# EXO-IMU3.net
KiCad netlist of a schematic drawn in EasyEDA Pro
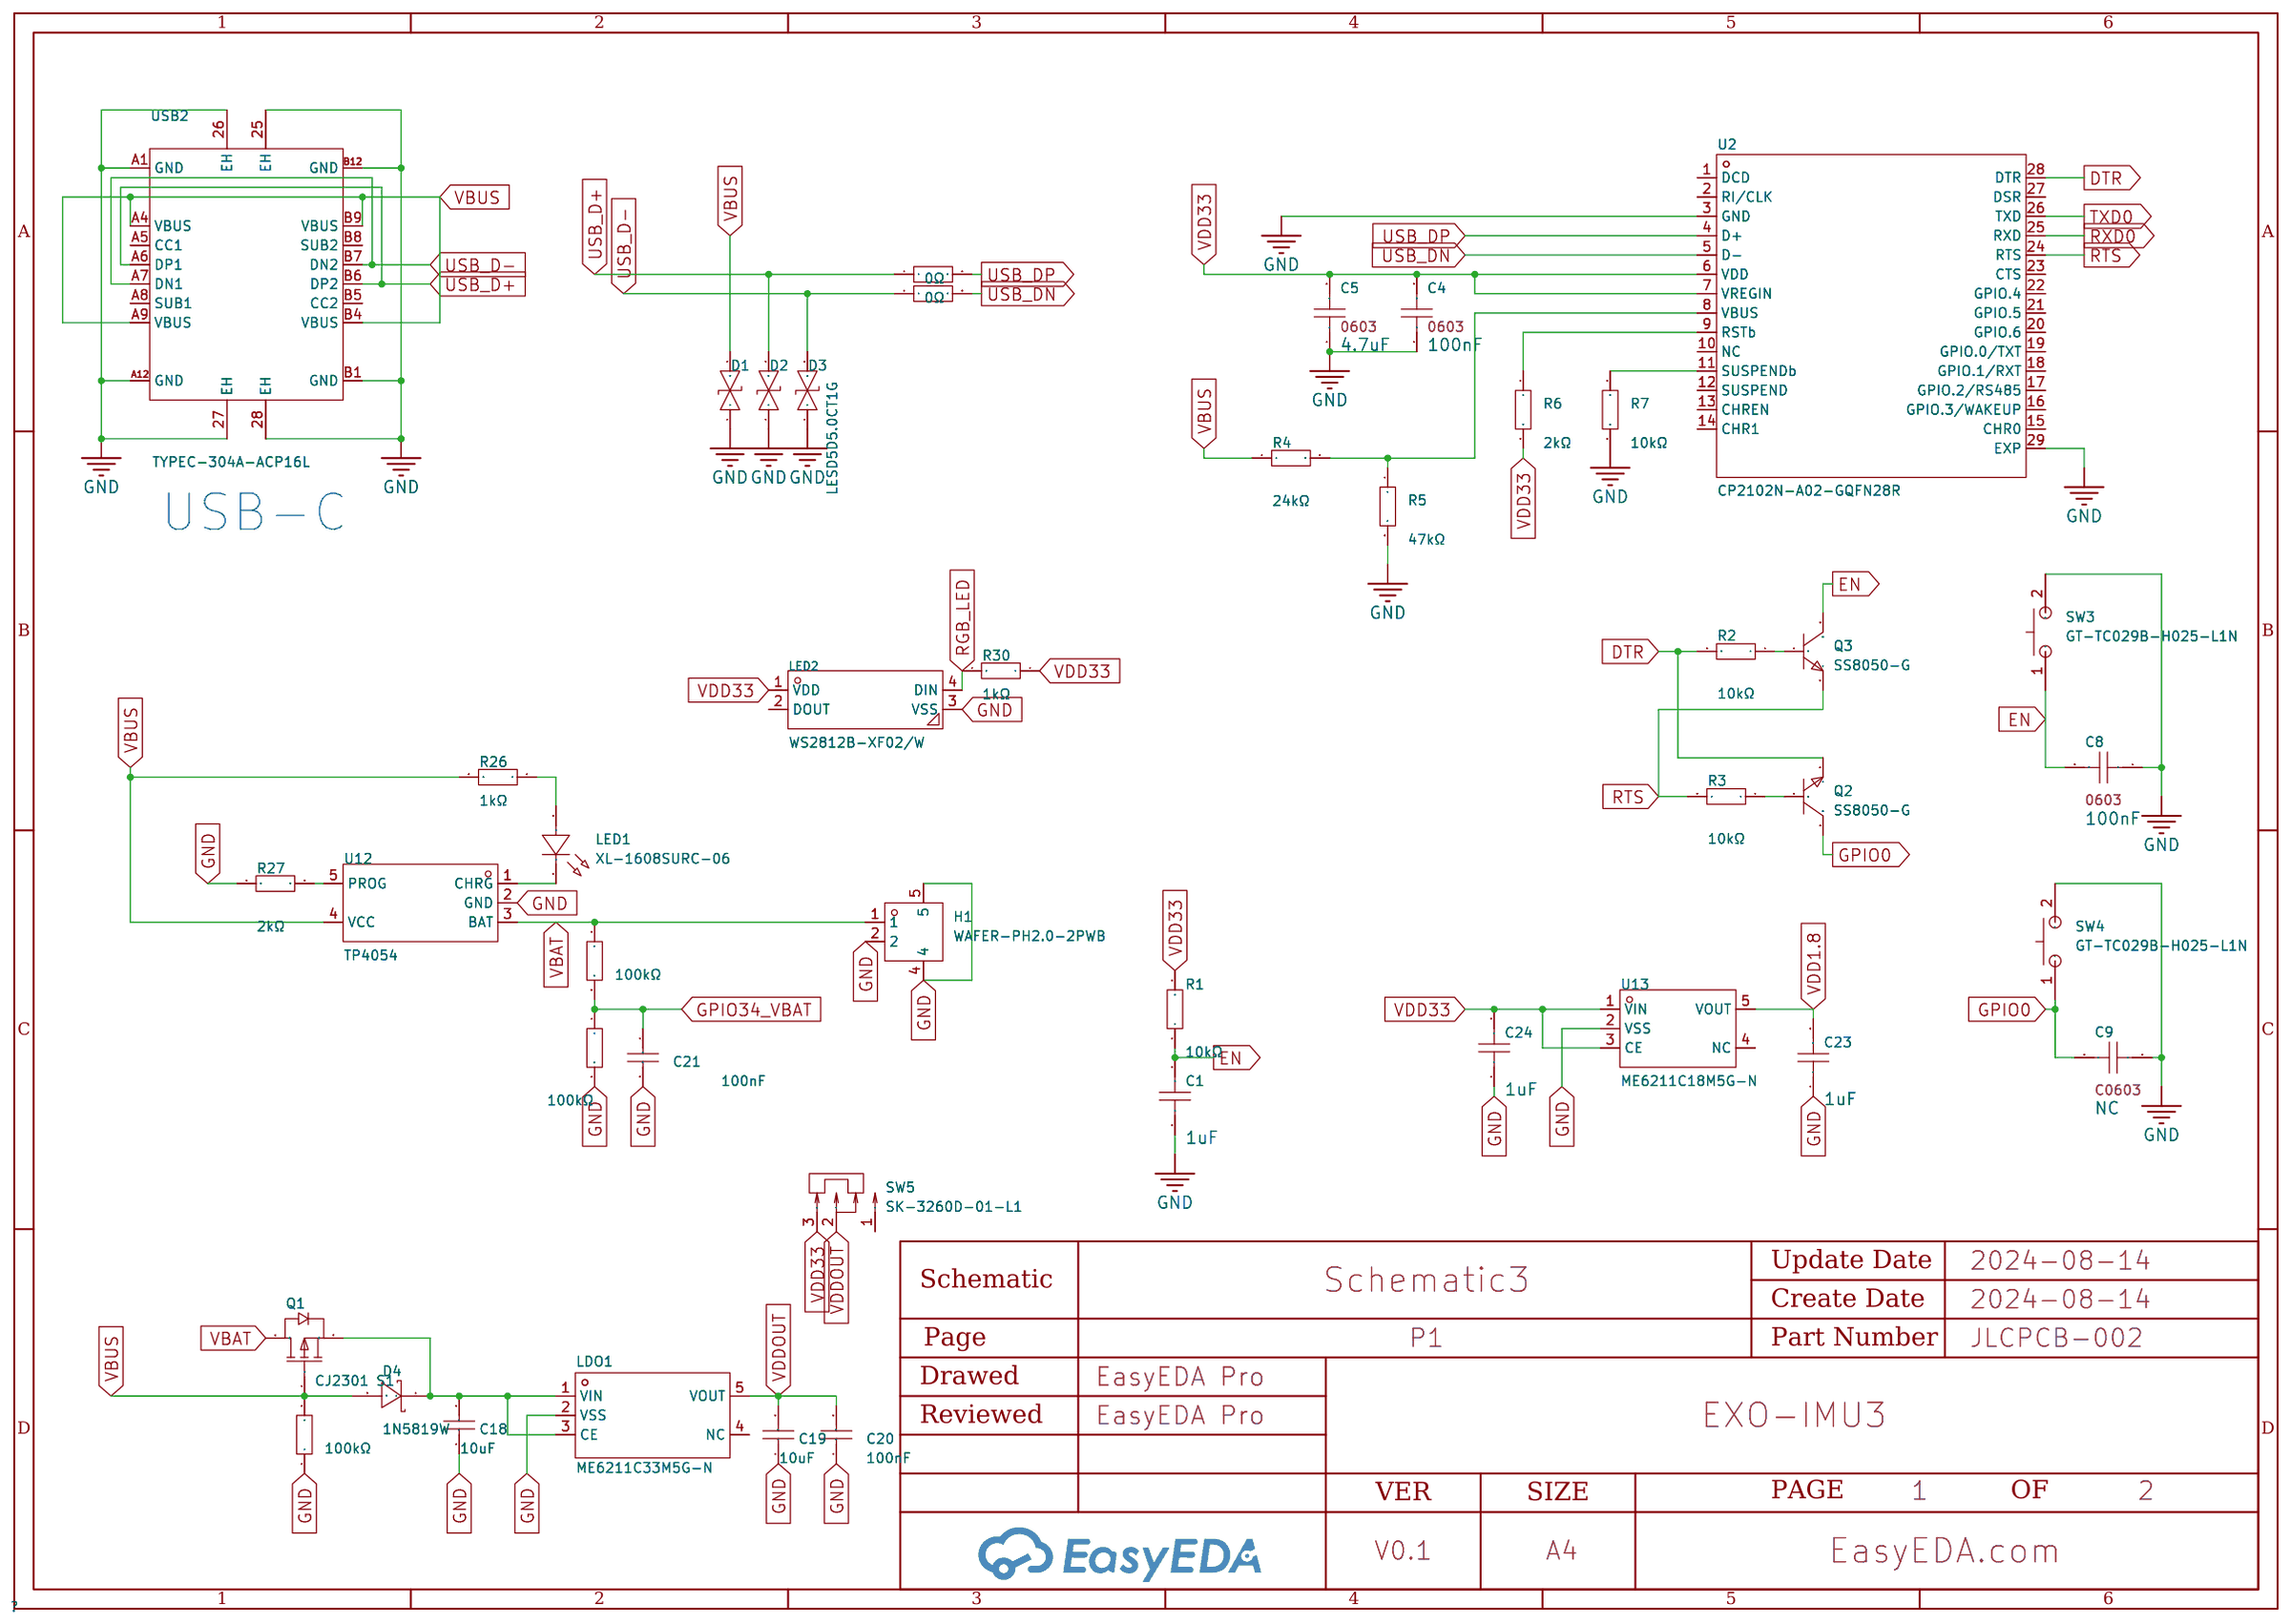
[diagram p0: P1]
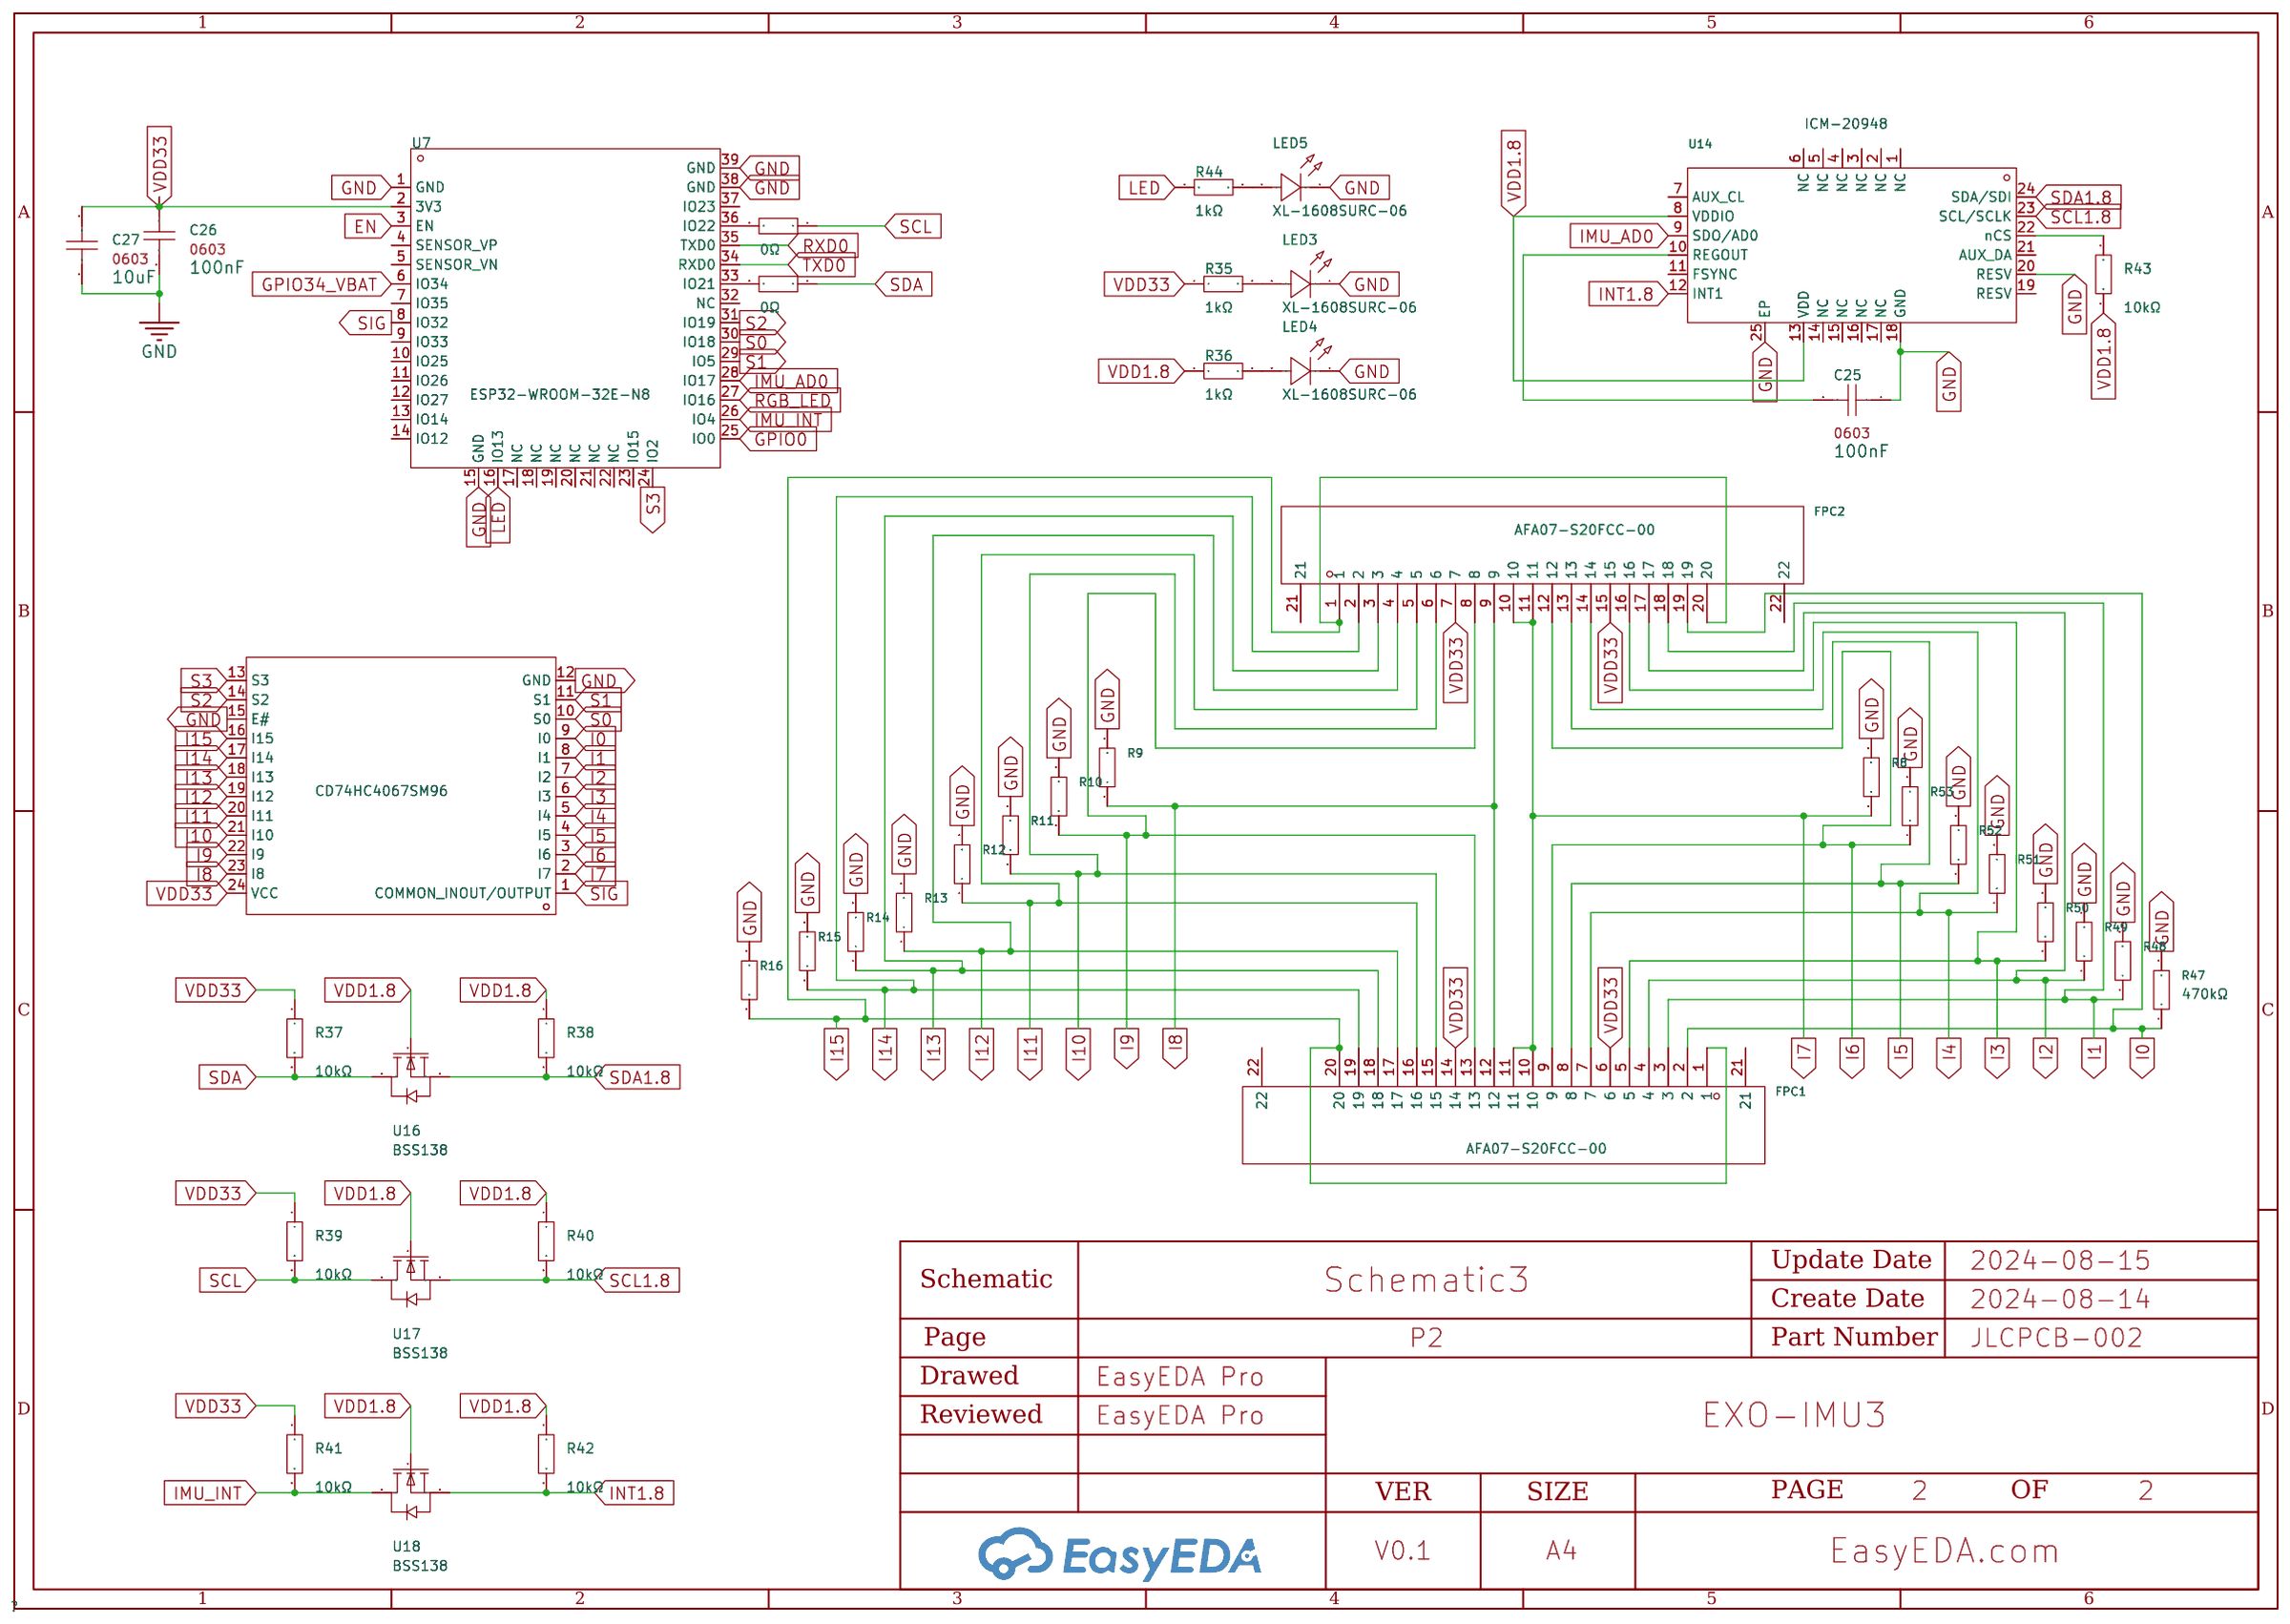
[diagram p1: P2]

(export (version "E")
  (design (tool "Eeschema 10.0.6"))
  (components
    (comp (ref "C1")
      (value "1uF")
      (footprint "easyedapro:C0603")
      (fields
        (field (name "Manufacturer Part") "CL10B105KO8NNNC")
        (field (name "Manufacturer") "SAMSUNG(三星)")
      )
      (libsource (lib "easyedapro") (part "CL10A106KP8NNNC"))
    )
    (comp (ref "C4")
      (value "100nF")
      (footprint "easyedapro:C0603")
      (fields
        (field (name "Manufacturer Part") "CC0603KRX7R6BB104")
        (field (name "Manufacturer") "YAGEO(国巨)")
        (field (name "Supplier Footprint") "0603")
      )
      (libsource (lib "easyedapro") (part "CL10A106KP8NNNC"))
    )
    (comp (ref "C5")
      (value "4.7uF")
      (footprint "easyedapro:C0603")
      (fields
        (field (name "Manufacturer Part") "CL10A475KP8NNNC")
        (field (name "Manufacturer") "SAMSUNG(三星)")
        (field (name "Supplier Footprint") "0603")
      )
      (libsource (lib "easyedapro") (part "CL10A106KP8NNNC"))
    )
    (comp (ref "C8")
      (value "100nF")
      (footprint "easyedapro:C0603")
      (fields
        (field (name "Manufacturer Part") "CC0603KRX7R6BB104")
        (field (name "Manufacturer") "YAGEO(国巨)")
        (field (name "Supplier Footprint") "0603")
      )
      (libsource (lib "easyedapro") (part "CL10A106KP8NNNC"))
    )
    (comp (ref "C9")
      (value "NC")
      (footprint "easyedapro:C0603")
      (fields (field (name "Manufacturer Part") "0603") (field (name "Supplier Footprint") "C0603"))
      (libsource (lib "easyedapro") (part "CL10A106KP8NNNC"))
    )
    (comp (ref "C18")
      (value "10uF")
      (fields
        (field (name "Manufacturer Part") "CL10A106KP8NNNC")
        (field (name "Manufacturer") "SAMSUNG(三星)")
      )
      (libsource (lib "easyedapro") (part "CL10A106MO8NQNC"))
    )
    (comp (ref "C19")
      (value "10uF")
      (fields
        (field (name "Manufacturer Part") "CL10A106KP8NNNC")
        (field (name "Manufacturer") "SAMSUNG(三星)")
      )
      (libsource (lib "easyedapro") (part "CL10A106MO8NQNC"))
    )
    (comp (ref "C20")
      (value "100nF")
      (fields
        (field (name "Manufacturer Part") "CC0603KRX7R6BB104")
        (field (name "Manufacturer") "YAGEO(国巨)")
      )
      (libsource (lib "easyedapro") (part "CL10B104KO8NNNC"))
    )
    (comp (ref "C21")
      (value "100nF")
      (fields
        (field (name "Manufacturer Part") "CC0603KRX7R6BB104")
        (field (name "Manufacturer") "YAGEO(国巨)")
      )
      (libsource (lib "easyedapro") (part "CL10B104KO8NNNC"))
    )
    (comp (ref "C23")
      (value "1uF")
      (footprint "easyedapro:C0603")
      (fields
        (field (name "Manufacturer Part") "CL10B105KO8NNNC")
        (field (name "Manufacturer") "SAMSUNG(三星)")
      )
      (libsource (lib "easyedapro") (part "CL10A106KP8NNNC"))
    )
    (comp (ref "C24")
      (value "1uF")
      (footprint "easyedapro:C0603")
      (fields
        (field (name "Manufacturer Part") "CL10B105KO8NNNC")
        (field (name "Manufacturer") "SAMSUNG(三星)")
      )
      (libsource (lib "easyedapro") (part "CL10A106KP8NNNC"))
    )
    (comp (ref "D1")
      (value "LESD5D5.0CT1G")
      (footprint "easyedapro:SOD-523_L1.2-W0.8-LS1.6-BI")
      (fields (field (name "Manufacturer") "LRC(乐山无线电)"))
      (libsource (lib "easyedapro") (part "LESD5D5.0CT1G"))
    )
    (comp (ref "D2")
      (value "LESD5D5.0CT1G")
      (footprint "easyedapro:SOD-523_L1.2-W0.8-LS1.6-BI")
      (fields (field (name "Manufacturer") "LRC(乐山无线电)"))
      (libsource (lib "easyedapro") (part "LESD5D5.0CT1G"))
    )
    (comp (ref "D3")
      (value "LESD5D5.0CT1G")
      (footprint "easyedapro:SOD-523_L1.2-W0.8-LS1.6-BI")
      (fields (field (name "Manufacturer") "LRC(乐山无线电)"))
      (libsource (lib "easyedapro") (part "LESD5D5.0CT1G"))
    )
    (comp (ref "D4")
      (value "1N5819W")
      (footprint "easyedapro:SOD-123F_L2.8-W1.8-LS3.7-RD")
      (description "Reverse Voltage (Vr):40V Average Rectified Current (Io):1A Forward Voltage (Vf@If):600mV@1A")
      (fields (field (name "Manufacturer") "晶导微电子"))
      (libsource (lib "easyedapro") (part "1N5819W"))
    )
    (comp (ref "H1")
      (value "WAFER-PH2.0-2PWB")
      (footprint "easyedapro:CONN-SMD_2P-P2.00_XUNPU_WAFER-PH2.0-2PWB")
      (fields (field (name "Manufacturer") "XUNPU(讯普)"))
      (libsource (lib "easyedapro") (part "WAFER-PH2.0-2PWB"))
    )
    (comp (ref "LDO1")
      (value "ME6211C33M5G-N")
      (footprint "easyedapro:SOT-23-5_L3.0-W1.7-P0.95-LS2.8-BL")
      (fields (field (name "Manufacturer") "MICRONE(南京微盟)"))
      (libsource (lib "easyedapro") (part "ME6211C33M5G-N"))
    )
    (comp (ref "LED1")
      (value "XL-1608SURC-06")
      (footprint "easyedapro:LED0603-RD_RED")
      (fields (field (name "Manufacturer") "XINGLIGHT(成兴光)"))
      (libsource (lib "easyedapro") (part "XL-1608SURC-06"))
    )
    (comp (ref "LED2")
      (value "WS2812B-XF02/W")
      (footprint "easyedapro:LED-SMD_4P-L5.0-W5.0-TL")
      (fields (field (name "Manufacturer") "worldsemi"))
      (libsource (lib "easyedapro") (part "WS2812B-XF02/W"))
    )
    (comp (ref "Q1")
      (value "CJ2301 S1")
      (footprint "easyedapro:SOT-23-3_L3.0-W1.7-P0.95-LS2.9-BR")
      (fields (field (name "Manufacturer") "CJ(江苏长电/长晶)"))
      (libsource (lib "easyedapro") (part "CJ2301 S1"))
    )
    (comp (ref "Q2")
      (value "SS8050-G")
      (footprint "easyedapro:SOT-23-3_L2.9-W1.3-P1.90-LS2.4-BR")
      (fields (field (name "Manufacturer") "CJ（江苏长电/长晶）"))
      (libsource (lib "easyedapro") (part "SS8050-G_C164885"))
    )
    (comp (ref "Q3")
      (value "SS8050-G")
      (footprint "easyedapro:SOT-23-3_L2.9-W1.3-P1.90-LS2.4-BR")
      (fields (field (name "Manufacturer") "CJ（江苏长电/长晶）"))
      (libsource (lib "easyedapro") (part "SS8050-G_C164885"))
    )
    (comp (ref "R1")
      (value "10kΩ")
      (footprint "easyedapro:R0603")
      (fields (field (name "Manufacturer Part") "RC0603JR-0710KL") (field (name "Manufacturer") "YAGEO(国巨)"))
      (libsource (lib "easyedapro") (part "0603WAF0000T5E"))
    )
    (comp (ref "R2")
      (value "10kΩ")
      (footprint "easyedapro:R0603")
      (fields (field (name "Manufacturer Part") "RC0603JR-0710KL") (field (name "Manufacturer") "YAGEO(国巨)"))
      (libsource (lib "easyedapro") (part "0603WAF0000T5E"))
    )
    (comp (ref "R3")
      (value "10kΩ")
      (footprint "easyedapro:R0603")
      (fields (field (name "Manufacturer Part") "RC0603JR-0710KL") (field (name "Manufacturer") "YAGEO(国巨)"))
      (libsource (lib "easyedapro") (part "0603WAF0000T5E"))
    )
    (comp (ref "R4")
      (value "24kΩ")
      (footprint "easyedapro:R0603")
      (fields
        (field (name "Manufacturer Part") "0603WAF2402T5E")
        (field (name "Manufacturer") "UNI-ROYAL(厚声)")
      )
      (libsource (lib "easyedapro") (part "RC0603JR-0710KL"))
    )
    (comp (ref "R5")
      (value "47kΩ")
      (footprint "easyedapro:R0603")
      (fields (field (name "Manufacturer Part") "RC0603FR-0747KL") (field (name "Manufacturer") "YAGEO(国巨)"))
      (libsource (lib "easyedapro") (part "RC0603JR-0710KL"))
    )
    (comp (ref "R6")
      (value "2kΩ")
      (footprint "easyedapro:R0603")
      (fields
        (field (name "Manufacturer Part") "0603WAF2001T5E")
        (field (name "Manufacturer") "UNI-ROYAL(厚声)")
      )
      (libsource (lib "easyedapro") (part "RC0603JR-0710KL"))
    )
    (comp (ref "R7")
      (value "10kΩ")
      (footprint "easyedapro:R0603")
      (fields (field (name "Manufacturer Part") "RC0603JR-0710KL") (field (name "Manufacturer") "YAGEO(国巨)"))
      (libsource (lib "easyedapro") (part "0603WAF0000T5E"))
    )
    (comp (ref "R21")
      (value "0Ω")
      (footprint "easyedapro:R0603")
      (fields
        (field (name "Manufacturer Part") "0603WAF0000T5E")
        (field (name "Manufacturer") "UNI-ROYAL(厚声)")
      )
      (libsource (lib "easyedapro") (part "RC0603JR-0710KL"))
    )
    (comp (ref "R22")
      (value "0Ω")
      (footprint "easyedapro:R0603")
      (fields
        (field (name "Manufacturer Part") "0603WAF0000T5E")
        (field (name "Manufacturer") "UNI-ROYAL(厚声)")
      )
      (libsource (lib "easyedapro") (part "RC0603JR-0710KL"))
    )
    (comp (ref "R25")
      (value "100kΩ")
      (footprint "easyedapro:R0603")
      (fields
        (field (name "Manufacturer Part") "0603WAF1003T5E")
        (field (name "Manufacturer") "UNI-ROYAL(厚声)")
      )
      (libsource (lib "easyedapro") (part "RC0603JR-0710KL"))
    )
    (comp (ref "R26")
      (value "1kΩ")
      (footprint "easyedapro:R0603")
      (fields
        (field (name "Manufacturer Part") "0603WAF1001T5E")
        (field (name "Manufacturer") "UNI-ROYAL(厚声)")
      )
      (libsource (lib "easyedapro") (part "0603WAF1001T5E"))
    )
    (comp (ref "R27")
      (value "2kΩ")
      (footprint "easyedapro:R0603")
      (fields
        (field (name "Manufacturer Part") "0603WAF2001T5E")
        (field (name "Manufacturer") "UNI-ROYAL(厚声)")
      )
      (libsource (lib "easyedapro") (part "RC0603JR-0710KL"))
    )
    (comp (ref "R28")
      (value "100kΩ")
      (footprint "easyedapro:R0603")
      (fields
        (field (name "Manufacturer Part") "0603WAF1003T5E")
        (field (name "Manufacturer") "UNI-ROYAL(厚声)")
      )
      (libsource (lib "easyedapro") (part "RC0603JR-0710KL"))
    )
    (comp (ref "R29")
      (value "100kΩ")
      (footprint "easyedapro:R0603")
      (fields
        (field (name "Manufacturer Part") "0603WAF1003T5E")
        (field (name "Manufacturer") "UNI-ROYAL(厚声)")
      )
      (libsource (lib "easyedapro") (part "RC0603JR-0710KL"))
    )
    (comp (ref "R30")
      (value "1kΩ")
      (footprint "easyedapro:R0603")
      (fields
        (field (name "Manufacturer Part") "0603WAF1001T5E")
        (field (name "Manufacturer") "UNI-ROYAL(厚声)")
      )
      (libsource (lib "easyedapro") (part "0603WAF1001T5E"))
    )
    (comp (ref "SW3")
      (value "GT-TC029B-H025-L1N")
      (footprint "easyedapro:SW-SMD_L3.9-W3.0-P4.45")
      (fields (field (name "Manufacturer") "G-Switch(品赞)"))
      (libsource (lib "easyedapro") (part "GT-TC029B-H025-L1N"))
    )
    (comp (ref "SW4")
      (value "GT-TC029B-H025-L1N")
      (footprint "easyedapro:SW-SMD_L3.9-W3.0-P4.45")
      (fields (field (name "Manufacturer") "G-Switch(品赞)"))
      (libsource (lib "easyedapro") (part "GT-TC029B-H025-L1N"))
    )
    (comp (ref "SW5")
      (value "SK-3260D-01-L1")
      (footprint "easyedapro:SW-TH_SK-3260D-01-LX")
      (fields (field (name "Manufacturer") "XKB Connectivity(中国星坤)"))
      (libsource (lib "easyedapro") (part "SK-3260D-01-L1"))
    )
    (comp (ref "U2")
      (value "CP2102N-A02-GQFN28R")
      (fields (field (name "Manufacturer") "SILICON LABS(芯科)"))
      (libsource (lib "easyedapro") (part "CP2102N-A01-GQFN28"))
    )
    (comp (ref "U12")
      (value "TP4054")
      (footprint "easyedapro:SOT-23-5_L2.9-W1.6-P0.95-LS2.8-BR")
      (fields (field (name "Manufacturer") "JSMSEMI(杰盛微)"))
      (libsource (lib "easyedapro") (part "TP4054_C5381776"))
    )
    (comp (ref "U13")
      (value "ME6211C18M5G-N")
      (footprint "easyedapro:SOT-23-5_L3.0-W1.7-P0.95-LS2.8-BR")
      (fields (field (name "Manufacturer") "MICRONE(南京微盟)"))
      (libsource (lib "easyedapro") (part "ME6211C18M5G-N"))
    )
    (comp (ref "USB2")
      (value "TYPEC-304A-ACP16L")
      (footprint "easyedapro:USB-C-SMD_XUNPU_TYPEC-304A-ACP16L")
      (fields (field (name "Manufacturer") "XUNPU(讯普)"))
      (libsource (lib "easyedapro") (part "TYPEC-304A-ACP16L"))
    )
    (comp (ref "C25")
      (value "100nF")
      (footprint "easyedapro:C0603")
      (fields
        (field (name "Manufacturer Part") "CC0603KRX7R6BB104")
        (field (name "Manufacturer") "YAGEO(国巨)")
        (field (name "Supplier Footprint") "0603")
      )
      (libsource (lib "easyedapro") (part "CL10A106KP8NNNC"))
    )
    (comp (ref "C26")
      (value "100nF")
      (footprint "easyedapro:C0603")
      (fields
        (field (name "Manufacturer Part") "CC0603KRX7R6BB104")
        (field (name "Manufacturer") "YAGEO(国巨)")
        (field (name "Supplier Footprint") "0603")
      )
      (libsource (lib "easyedapro") (part "0603_C9900021180"))
    )
    (comp (ref "C27")
      (value "10uF")
      (footprint "easyedapro:C0603")
      (fields
        (field (name "Manufacturer Part") "CL10A106KP8NNNC")
        (field (name "Manufacturer") "SAMSUNG(三星)")
        (field (name "Supplier Footprint") "0603")
      )
      (libsource (lib "easyedapro") (part "0603_C9900021180"))
    )
    (comp (ref "FPC1")
      (value "AFA07-S20FCC-00")
      (footprint "easyedapro:FPC-SMD_AFA07-S20FCC-00")
      (fields (field (name "Manufacturer") "JS(钜硕电子)"))
      (libsource (lib "easyedapro") (part "AFA07-S20FCC-00"))
    )
    (comp (ref "FPC2")
      (value "AFA07-S20FCC-00")
      (footprint "easyedapro:FPC-SMD_AFA07-S20FCC-00")
      (fields (field (name "Manufacturer") "JS(钜硕电子)"))
      (libsource (lib "easyedapro") (part "AFA07-S20FCC-00"))
    )
    (comp (ref "LED3")
      (value "XL-1608SURC-06")
      (footprint "easyedapro:LED0603-RD_RED")
      (fields (field (name "Manufacturer") "XINGLIGHT(成兴光)"))
      (libsource (lib "easyedapro") (part "XL-1608SURC-06"))
    )
    (comp (ref "LED4")
      (value "XL-1608SURC-06")
      (footprint "easyedapro:LED0603-RD_RED")
      (fields (field (name "Manufacturer") "XINGLIGHT(成兴光)"))
      (libsource (lib "easyedapro") (part "XL-1608SURC-06"))
    )
    (comp (ref "LED5")
      (value "XL-1608SURC-06")
      (footprint "easyedapro:LED0603-RD_RED")
      (fields (field (name "Manufacturer") "XINGLIGHT(成兴光)"))
      (libsource (lib "easyedapro") (part "XL-1608SURC-06"))
    )
    (comp (ref "R8")
      (value "470kΩ")
      (footprint "easyedapro:R0805")
      (fields
        (field (name "Manufacturer Part") "0805W8F4703T5E")
        (field (name "Manufacturer") "UNI-ROYAL(厚声)")
      )
      (libsource (lib "easyedapro") (part "0805W8F4703T5E"))
    )
    (comp (ref "R9")
      (value "470kΩ")
      (footprint "easyedapro:R0805")
      (fields
        (field (name "Manufacturer Part") "0805W8F4703T5E")
        (field (name "Manufacturer") "UNI-ROYAL(厚声)")
      )
      (libsource (lib "easyedapro") (part "0805W8F4703T5E"))
    )
    (comp (ref "R10")
      (value "470kΩ")
      (footprint "easyedapro:R0805")
      (fields
        (field (name "Manufacturer Part") "0805W8F4703T5E")
        (field (name "Manufacturer") "UNI-ROYAL(厚声)")
      )
      (libsource (lib "easyedapro") (part "0805W8F4703T5E"))
    )
    (comp (ref "R11")
      (value "470kΩ")
      (footprint "easyedapro:R0805")
      (fields
        (field (name "Manufacturer Part") "0805W8F4703T5E")
        (field (name "Manufacturer") "UNI-ROYAL(厚声)")
      )
      (libsource (lib "easyedapro") (part "0805W8F4703T5E"))
    )
    (comp (ref "R12")
      (value "470kΩ")
      (footprint "easyedapro:R0805")
      (fields
        (field (name "Manufacturer Part") "0805W8F4703T5E")
        (field (name "Manufacturer") "UNI-ROYAL(厚声)")
      )
      (libsource (lib "easyedapro") (part "0805W8F4703T5E"))
    )
    (comp (ref "R13")
      (value "470kΩ")
      (footprint "easyedapro:R0805")
      (fields
        (field (name "Manufacturer Part") "0805W8F4703T5E")
        (field (name "Manufacturer") "UNI-ROYAL(厚声)")
      )
      (libsource (lib "easyedapro") (part "0805W8F4703T5E"))
    )
    (comp (ref "R14")
      (value "470kΩ")
      (footprint "easyedapro:R0805")
      (fields
        (field (name "Manufacturer Part") "0805W8F4703T5E")
        (field (name "Manufacturer") "UNI-ROYAL(厚声)")
      )
      (libsource (lib "easyedapro") (part "0805W8F4703T5E"))
    )
    (comp (ref "R15")
      (value "470kΩ")
      (footprint "easyedapro:R0805")
      (fields
        (field (name "Manufacturer Part") "0805W8F4703T5E")
        (field (name "Manufacturer") "UNI-ROYAL(厚声)")
      )
      (libsource (lib "easyedapro") (part "0805W8F4703T5E"))
    )
    (comp (ref "R16")
      (value "470kΩ")
      (footprint "easyedapro:R0805")
      (fields
        (field (name "Manufacturer Part") "0805W8F4703T5E")
        (field (name "Manufacturer") "UNI-ROYAL(厚声)")
      )
      (libsource (lib "easyedapro") (part "0805W8F4703T5E"))
    )
    (comp (ref "R35")
      (value "1kΩ")
      (footprint "easyedapro:R0603")
      (fields
        (field (name "Manufacturer Part") "0603WAF1001T5E")
        (field (name "Manufacturer") "UNI-ROYAL(厚声)")
      )
      (libsource (lib "easyedapro") (part "0603WAF1001T5E"))
    )
    (comp (ref "R36")
      (value "1kΩ")
      (footprint "easyedapro:R0603")
      (fields
        (field (name "Manufacturer Part") "0603WAF1001T5E")
        (field (name "Manufacturer") "UNI-ROYAL(厚声)")
      )
      (libsource (lib "easyedapro") (part "0603WAF1001T5E"))
    )
    (comp (ref "R37")
      (value "10kΩ")
      (footprint "easyedapro:R0603")
      (fields (field (name "Manufacturer Part") "RC0603JR-0710KL") (field (name "Manufacturer") "YAGEO(国巨)"))
      (libsource (lib "easyedapro") (part "0603WAF0000T5E"))
    )
    (comp (ref "R38")
      (value "10kΩ")
      (footprint "easyedapro:R0603")
      (fields (field (name "Manufacturer Part") "RC0603JR-0710KL") (field (name "Manufacturer") "YAGEO(国巨)"))
      (libsource (lib "easyedapro") (part "0603WAF0000T5E"))
    )
    (comp (ref "R39")
      (value "10kΩ")
      (footprint "easyedapro:R0603")
      (fields (field (name "Manufacturer Part") "RC0603JR-0710KL") (field (name "Manufacturer") "YAGEO(国巨)"))
      (libsource (lib "easyedapro") (part "0603WAF0000T5E"))
    )
    (comp (ref "R40")
      (value "10kΩ")
      (footprint "easyedapro:R0603")
      (fields (field (name "Manufacturer Part") "RC0603JR-0710KL") (field (name "Manufacturer") "YAGEO(国巨)"))
      (libsource (lib "easyedapro") (part "0603WAF0000T5E"))
    )
    (comp (ref "R41")
      (value "10kΩ")
      (footprint "easyedapro:R0603")
      (fields (field (name "Manufacturer Part") "RC0603JR-0710KL") (field (name "Manufacturer") "YAGEO(国巨)"))
      (libsource (lib "easyedapro") (part "0603WAF0000T5E"))
    )
    (comp (ref "R42")
      (value "10kΩ")
      (footprint "easyedapro:R0603")
      (fields (field (name "Manufacturer Part") "RC0603JR-0710KL") (field (name "Manufacturer") "YAGEO(国巨)"))
      (libsource (lib "easyedapro") (part "0603WAF0000T5E"))
    )
    (comp (ref "R43")
      (value "10kΩ")
      (footprint "easyedapro:R0603")
      (fields (field (name "Manufacturer Part") "RC0603JR-0710KL") (field (name "Manufacturer") "YAGEO(国巨)"))
      (libsource (lib "easyedapro") (part "0603WAF0000T5E"))
    )
    (comp (ref "R44")
      (value "1kΩ")
      (footprint "easyedapro:R0603")
      (fields
        (field (name "Manufacturer Part") "0603WAF1001T5E")
        (field (name "Manufacturer") "UNI-ROYAL(厚声)")
      )
      (libsource (lib "easyedapro") (part "0603WAF1001T5E"))
    )
    (comp (ref "R45")
      (value "0Ω")
      (footprint "easyedapro:R0603")
      (fields
        (field (name "Manufacturer Part") "0603WAF0000T5E")
        (field (name "Manufacturer") "UNI-ROYAL(厚声)")
      )
      (libsource (lib "easyedapro") (part "RC0603JR-0710KL"))
    )
    (comp (ref "R46")
      (value "0Ω")
      (footprint "easyedapro:R0603")
      (fields
        (field (name "Manufacturer Part") "0603WAF0000T5E")
        (field (name "Manufacturer") "UNI-ROYAL(厚声)")
      )
      (libsource (lib "easyedapro") (part "RC0603JR-0710KL"))
    )
    (comp (ref "R47")
      (value "470kΩ")
      (footprint "easyedapro:R0805")
      (fields
        (field (name "Manufacturer Part") "0805W8F4703T5E")
        (field (name "Manufacturer") "UNI-ROYAL(厚声)")
      )
      (libsource (lib "easyedapro") (part "0805W8F4703T5E"))
    )
    (comp (ref "R48")
      (value "470kΩ")
      (footprint "easyedapro:R0805")
      (fields
        (field (name "Manufacturer Part") "0805W8F4703T5E")
        (field (name "Manufacturer") "UNI-ROYAL(厚声)")
      )
      (libsource (lib "easyedapro") (part "0805W8F4703T5E"))
    )
    (comp (ref "R49")
      (value "470kΩ")
      (footprint "easyedapro:R0805")
      (fields
        (field (name "Manufacturer Part") "0805W8F4703T5E")
        (field (name "Manufacturer") "UNI-ROYAL(厚声)")
      )
      (libsource (lib "easyedapro") (part "0805W8F4703T5E"))
    )
    (comp (ref "R50")
      (value "470kΩ")
      (footprint "easyedapro:R0805")
      (fields
        (field (name "Manufacturer Part") "0805W8F4703T5E")
        (field (name "Manufacturer") "UNI-ROYAL(厚声)")
      )
      (libsource (lib "easyedapro") (part "0805W8F4703T5E"))
    )
    (comp (ref "R51")
      (value "470kΩ")
      (footprint "easyedapro:R0805")
      (fields
        (field (name "Manufacturer Part") "0805W8F4703T5E")
        (field (name "Manufacturer") "UNI-ROYAL(厚声)")
      )
      (libsource (lib "easyedapro") (part "0805W8F4703T5E"))
    )
    (comp (ref "R52")
      (value "470kΩ")
      (footprint "easyedapro:R0805")
      (fields
        (field (name "Manufacturer Part") "0805W8F4703T5E")
        (field (name "Manufacturer") "UNI-ROYAL(厚声)")
      )
      (libsource (lib "easyedapro") (part "0805W8F4703T5E"))
    )
    (comp (ref "R53")
      (value "470kΩ")
      (footprint "easyedapro:R0805")
      (fields
        (field (name "Manufacturer Part") "0805W8F4703T5E")
        (field (name "Manufacturer") "UNI-ROYAL(厚声)")
      )
      (libsource (lib "easyedapro") (part "0805W8F4703T5E"))
    )
    (comp (ref "U7")
      (value "ESP32-WROOM-32E-N8")
      (footprint "easyedapro:WIFI-SMD_ESP32-WROOM-32E")
      (fields (field (name "Manufacturer") "ESPRESSIF(乐鑫)"))
      (libsource (lib "easyedapro") (part "ESP32-WROOM-32E-N8"))
    )
    (comp (ref "U14")
      (value "ICM-20948")
      (footprint "easyedapro:QFN-24_L3.0-W3.0-P0.40-BL-EP")
      (description "Sensor Type:加速度计陀螺仪 Operating Temperature:-40°C~+85°C Operating Temperature:-40°C~+85°C")
      (fields (field (name "Manufacturer") "TDK InvenSense(应美盛)"))
      (libsource (lib "easyedapro") (part "ICM-20948"))
    )
    (comp (ref "U16")
      (value "BSS138")
      (footprint "easyedapro:SOT-23-3_L2.9-W1.3-P1.90-LS2.4-BR")
      (fields (field (name "Manufacturer") "宏迦橙"))
      (libsource (lib "easyedapro") (part "BSS138_C7420339"))
    )
    (comp (ref "U17")
      (value "BSS138")
      (footprint "easyedapro:SOT-23-3_L2.9-W1.3-P1.90-LS2.4-BR")
      (fields (field (name "Manufacturer") "宏迦橙"))
      (libsource (lib "easyedapro") (part "BSS138_C7420339"))
    )
    (comp (ref "U18")
      (value "BSS138")
      (footprint "easyedapro:SOT-23-3_L2.9-W1.3-P1.90-LS2.4-BR")
      (fields (field (name "Manufacturer") "宏迦橙"))
      (libsource (lib "easyedapro") (part "BSS138_C7420339"))
    )
    (comp (ref "U19")
      (value "CD74HC4067SM96")
      (footprint "easyedapro:SSOP-24_L8.1-W5.3-P0.65-LS7.8-BL")
      (description "Switch Circuit:-")
      (fields (field (name "Manufacturer") "TI(德州仪器)"))
      (libsource (lib "easyedapro") (part "CD74HC4067SM96"))
    )
  )
  (nets
    (net (code "1") (name "DTR") (class "Default")
      (node (ref "Q2") (pin "2") (pinfunction "E_2") (pintype "input"))
      (node (ref "R2") (pin "2") (pinfunction "2_2") (pintype "input"))
      (node (ref "U2") (pin "28") (pinfunction "DTR_28") (pintype "input"))
    )
    (net (code "2") (name "EN") (class "Default")
      (node (ref "C1") (pin "2") (pinfunction "2_2") (pintype "input"))
      (node (ref "C8") (pin "2") (pinfunction "2_2") (pintype "input"))
      (node (ref "Q3") (pin "3") (pinfunction "C_3") (pintype "input"))
      (node (ref "R1") (pin "1") (pinfunction "1_1") (pintype "input"))
      (node (ref "SW3") (pin "1") (pinfunction "1_1") (pintype "input"))
      (node (ref "U7") (pin "3") (pinfunction "EN_3") (pintype "input"))
    )
    (net (code "3") (name "GND") (class "Default")
      (node (ref "C1") (pin "1") (pinfunction "1_1") (pintype "input"))
      (node (ref "C18") (pin "1") (pinfunction "1_1") (pintype "input"))
      (node (ref "C19") (pin "1") (pinfunction "1_1") (pintype "input"))
      (node (ref "C20") (pin "1") (pinfunction "1_1") (pintype "input"))
      (node (ref "C21") (pin "2") (pinfunction "2_2") (pintype "input"))
      (node (ref "C23") (pin "1") (pinfunction "1_1") (pintype "input"))
      (node (ref "C24") (pin "1") (pinfunction "1_1") (pintype "input"))
      (node (ref "C25") (pin "1") (pinfunction "1_1") (pintype "input"))
      (node (ref "C26") (pin "1") (pinfunction "1_1") (pintype "input"))
      (node (ref "C27") (pin "1") (pinfunction "1_1") (pintype "input"))
      (node (ref "C4") (pin "1") (pinfunction "1_1") (pintype "input"))
      (node (ref "C5") (pin "1") (pinfunction "1_1") (pintype "input"))
      (node (ref "C8") (pin "1") (pinfunction "1_1") (pintype "input"))
      (node (ref "C9") (pin "1") (pinfunction "1_1") (pintype "input"))
      (node (ref "D1") (pin "1") (pinfunction "1_1") (pintype "input"))
      (node (ref "D2") (pin "1") (pinfunction "1_1") (pintype "input"))
      (node (ref "D3") (pin "1") (pinfunction "1_1") (pintype "input"))
      (node (ref "H1") (pin "2") (pinfunction "2_2") (pintype "input"))
      (node (ref "H1") (pin "4") (pinfunction "4_4") (pintype "input"))
      (node (ref "H1") (pin "5") (pinfunction "5_5") (pintype "input"))
      (node (ref "LDO1") (pin "2") (pinfunction "VSS_2") (pintype "input"))
      (node (ref "LED2") (pin "3") (pinfunction "VSS_3") (pintype "input"))
      (node (ref "LED3") (pin "1") (pinfunction "K_1") (pintype "input"))
      (node (ref "LED4") (pin "1") (pinfunction "K_1") (pintype "input"))
      (node (ref "LED5") (pin "1") (pinfunction "K_1") (pintype "input"))
      (node (ref "R10") (pin "2") (pinfunction "2_2") (pintype "input"))
      (node (ref "R11") (pin "2") (pinfunction "2_2") (pintype "input"))
      (node (ref "R12") (pin "2") (pinfunction "2_2") (pintype "input"))
      (node (ref "R13") (pin "2") (pinfunction "2_2") (pintype "input"))
      (node (ref "R14") (pin "2") (pinfunction "2_2") (pintype "input"))
      (node (ref "R15") (pin "2") (pinfunction "2_2") (pintype "input"))
      (node (ref "R16") (pin "2") (pinfunction "2_2") (pintype "input"))
      (node (ref "R25") (pin "1") (pinfunction "1_1") (pintype "input"))
      (node (ref "R27") (pin "1") (pinfunction "1_1") (pintype "input"))
      (node (ref "R28") (pin "2") (pinfunction "2_2") (pintype "input"))
      (node (ref "R47") (pin "2") (pinfunction "2_2") (pintype "input"))
      (node (ref "R48") (pin "2") (pinfunction "2_2") (pintype "input"))
      (node (ref "R49") (pin "2") (pinfunction "2_2") (pintype "input"))
      (node (ref "R5") (pin "2") (pinfunction "2_2") (pintype "input"))
      (node (ref "R50") (pin "2") (pinfunction "2_2") (pintype "input"))
      (node (ref "R51") (pin "2") (pinfunction "2_2") (pintype "input"))
      (node (ref "R52") (pin "2") (pinfunction "2_2") (pintype "input"))
      (node (ref "R53") (pin "2") (pinfunction "2_2") (pintype "input"))
      (node (ref "R7") (pin "2") (pinfunction "2_2") (pintype "input"))
      (node (ref "R8") (pin "2") (pinfunction "2_2") (pintype "input"))
      (node (ref "R9") (pin "2") (pinfunction "2_2") (pintype "input"))
      (node (ref "SW3") (pin "2") (pinfunction "2_2") (pintype "input"))
      (node (ref "SW4") (pin "2") (pinfunction "2_2") (pintype "input"))
      (node (ref "U12") (pin "2") (pinfunction "GND_2") (pintype "input"))
      (node (ref "U13") (pin "2") (pinfunction "VSS_2") (pintype "input"))
      (node (ref "U14") (pin "18") (pinfunction "GND_18") (pintype "input"))
      (node (ref "U14") (pin "20") (pinfunction "RESV_20") (pintype "input"))
      (node (ref "U14") (pin "25") (pinfunction "EP_25") (pintype "input"))
      (node (ref "U19") (pin "12") (pinfunction "GND_12") (pintype "unspecified"))
      (node (ref "U19") (pin "15") (pinfunction "E#_15") (pintype "unspecified"))
      (node (ref "U2") (pin "29") (pinfunction "EXP_29") (pintype "input"))
      (node (ref "U2") (pin "3") (pinfunction "GND_3") (pintype "input"))
      (node (ref "U7") (pin "1") (pinfunction "GND_1") (pintype "input"))
      (node (ref "U7") (pin "15") (pinfunction "GND_15") (pintype "input"))
      (node (ref "U7") (pin "38") (pinfunction "GND_38") (pintype "input"))
      (node (ref "U7") (pin "39") (pinfunction "GND_39") (pintype "input"))
      (node (ref "USB2") (pin "25") (pinfunction "EH_25") (pintype "input"))
      (node (ref "USB2") (pin "26") (pinfunction "EH_26") (pintype "input"))
      (node (ref "USB2") (pin "27") (pinfunction "EH_27") (pintype "input"))
      (node (ref "USB2") (pin "28") (pinfunction "EH_28") (pintype "input"))
      (node (ref "USB2") (pin "A1") (pinfunction "GND_A1") (pintype "input"))
      (node (ref "USB2") (pin "A12") (pinfunction "GND_A12") (pintype "input"))
      (node (ref "USB2") (pin "B1") (pinfunction "GND_B1") (pintype "input"))
      (node (ref "USB2") (pin "B12") (pinfunction "GND_B12") (pintype "input"))
    )
    (net (code "4") (name "GPIO0") (class "Default")
      (node (ref "C9") (pin "2") (pinfunction "2_2") (pintype "input"))
      (node (ref "Q2") (pin "3") (pinfunction "C_3") (pintype "input"))
      (node (ref "SW4") (pin "1") (pinfunction "1_1") (pintype "input"))
      (node (ref "U7") (pin "25") (pinfunction "IO0_25") (pintype "input"))
    )
    (net (code "5") (name "GPIO34_VBAT") (class "Default")
      (node (ref "C21") (pin "1") (pinfunction "1_1") (pintype "input"))
      (node (ref "R28") (pin "1") (pinfunction "1_1") (pintype "input"))
      (node (ref "R29") (pin "2") (pinfunction "2_2") (pintype "input"))
      (node (ref "U7") (pin "6") (pinfunction "IO34_6") (pintype "input"))
    )
    (net (code "6") (name "I0") (class "Default")
      (node (ref "FPC1") (pin "2") (pinfunction "2_2") (pintype "input"))
      (node (ref "FPC2") (pin "19") (pinfunction "19_19") (pintype "input"))
      (node (ref "R47") (pin "1") (pinfunction "1_1") (pintype "input"))
      (node (ref "U19") (pin "9") (pinfunction "I0_9") (pintype "unspecified"))
    )
    (net (code "7") (name "I1") (class "Default")
      (node (ref "FPC1") (pin "3") (pinfunction "3_3") (pintype "input"))
      (node (ref "FPC2") (pin "18") (pinfunction "18_18") (pintype "input"))
      (node (ref "R48") (pin "1") (pinfunction "1_1") (pintype "input"))
      (node (ref "U19") (pin "8") (pinfunction "I1_8") (pintype "unspecified"))
    )
    (net (code "8") (name "I2") (class "Default")
      (node (ref "FPC1") (pin "4") (pinfunction "4_4") (pintype "input"))
      (node (ref "FPC2") (pin "17") (pinfunction "17_17") (pintype "input"))
      (node (ref "R49") (pin "1") (pinfunction "1_1") (pintype "input"))
      (node (ref "U19") (pin "7") (pinfunction "I2_7") (pintype "unspecified"))
    )
    (net (code "9") (name "I3") (class "Default")
      (node (ref "FPC1") (pin "5") (pinfunction "5_5") (pintype "input"))
      (node (ref "FPC2") (pin "16") (pinfunction "16_16") (pintype "input"))
      (node (ref "R50") (pin "1") (pinfunction "1_1") (pintype "input"))
      (node (ref "U19") (pin "6") (pinfunction "I3_6") (pintype "unspecified"))
    )
    (net (code "10") (name "I4") (class "Default")
      (node (ref "FPC1") (pin "7") (pinfunction "7_7") (pintype "input"))
      (node (ref "FPC2") (pin "14") (pinfunction "14_14") (pintype "input"))
      (node (ref "R51") (pin "1") (pinfunction "1_1") (pintype "input"))
      (node (ref "U19") (pin "5") (pinfunction "I4_5") (pintype "unspecified"))
    )
    (net (code "11") (name "I5") (class "Default")
      (node (ref "FPC1") (pin "8") (pinfunction "8_8") (pintype "input"))
      (node (ref "FPC2") (pin "13") (pinfunction "13_13") (pintype "input"))
      (node (ref "R52") (pin "1") (pinfunction "1_1") (pintype "input"))
      (node (ref "U19") (pin "4") (pinfunction "I5_4") (pintype "unspecified"))
    )
    (net (code "12") (name "I6") (class "Default")
      (node (ref "FPC1") (pin "9") (pinfunction "9_9") (pintype "input"))
      (node (ref "FPC2") (pin "12") (pinfunction "12_12") (pintype "input"))
      (node (ref "R53") (pin "1") (pinfunction "1_1") (pintype "input"))
      (node (ref "U19") (pin "3") (pinfunction "I6_3") (pintype "unspecified"))
    )
    (net (code "13") (name "I7") (class "Default")
      (node (ref "FPC1") (pin "10") (pinfunction "10_10") (pintype "input"))
      (node (ref "FPC1") (pin "11") (pinfunction "11_11") (pintype "input"))
      (node (ref "FPC2") (pin "10") (pinfunction "10_10") (pintype "input"))
      (node (ref "FPC2") (pin "11") (pinfunction "11_11") (pintype "input"))
      (node (ref "R8") (pin "1") (pinfunction "1_1") (pintype "input"))
      (node (ref "U19") (pin "2") (pinfunction "I7_2") (pintype "unspecified"))
    )
    (net (code "14") (name "I8") (class "Default")
      (node (ref "FPC1") (pin "12") (pinfunction "12_12") (pintype "input"))
      (node (ref "FPC2") (pin "9") (pinfunction "9_9") (pintype "input"))
      (node (ref "R9") (pin "1") (pinfunction "1_1") (pintype "input"))
      (node (ref "U19") (pin "23") (pinfunction "I8_23") (pintype "unspecified"))
    )
    (net (code "15") (name "I9") (class "Default")
      (node (ref "FPC1") (pin "13") (pinfunction "13_13") (pintype "input"))
      (node (ref "FPC2") (pin "8") (pinfunction "8_8") (pintype "input"))
      (node (ref "R10") (pin "1") (pinfunction "1_1") (pintype "input"))
      (node (ref "U19") (pin "22") (pinfunction "I9_22") (pintype "unspecified"))
    )
    (net (code "16") (name "I10") (class "Default")
      (node (ref "FPC1") (pin "15") (pinfunction "15_15") (pintype "input"))
      (node (ref "FPC2") (pin "6") (pinfunction "6_6") (pintype "input"))
      (node (ref "R11") (pin "1") (pinfunction "1_1") (pintype "input"))
      (node (ref "U19") (pin "21") (pinfunction "I10_21") (pintype "unspecified"))
    )
    (net (code "17") (name "I11") (class "Default")
      (node (ref "FPC1") (pin "16") (pinfunction "16_16") (pintype "input"))
      (node (ref "FPC2") (pin "5") (pinfunction "5_5") (pintype "input"))
      (node (ref "R12") (pin "1") (pinfunction "1_1") (pintype "input"))
      (node (ref "U19") (pin "20") (pinfunction "I11_20") (pintype "unspecified"))
    )
    (net (code "18") (name "I12") (class "Default")
      (node (ref "FPC1") (pin "17") (pinfunction "17_17") (pintype "input"))
      (node (ref "FPC2") (pin "4") (pinfunction "4_4") (pintype "input"))
      (node (ref "R13") (pin "1") (pinfunction "1_1") (pintype "input"))
      (node (ref "U19") (pin "19") (pinfunction "I12_19") (pintype "unspecified"))
    )
    (net (code "19") (name "I13") (class "Default")
      (node (ref "FPC1") (pin "18") (pinfunction "18_18") (pintype "input"))
      (node (ref "FPC2") (pin "3") (pinfunction "3_3") (pintype "input"))
      (node (ref "R14") (pin "1") (pinfunction "1_1") (pintype "input"))
      (node (ref "U19") (pin "18") (pinfunction "I13_18") (pintype "unspecified"))
    )
    (net (code "20") (name "I14") (class "Default")
      (node (ref "FPC1") (pin "19") (pinfunction "19_19") (pintype "input"))
      (node (ref "FPC2") (pin "2") (pinfunction "2_2") (pintype "input"))
      (node (ref "R15") (pin "1") (pinfunction "1_1") (pintype "input"))
      (node (ref "U19") (pin "17") (pinfunction "I14_17") (pintype "unspecified"))
    )
    (net (code "21") (name "I15") (class "Default")
      (node (ref "FPC1") (pin "1") (pinfunction "1_1") (pintype "input"))
      (node (ref "FPC1") (pin "20") (pinfunction "20_20") (pintype "input"))
      (node (ref "FPC2") (pin "1") (pinfunction "1_1") (pintype "input"))
      (node (ref "FPC2") (pin "20") (pinfunction "20_20") (pintype "input"))
      (node (ref "R16") (pin "1") (pinfunction "1_1") (pintype "input"))
      (node (ref "U19") (pin "16") (pinfunction "I15_16") (pintype "unspecified"))
    )
    (net (code "22") (name "IMU_AD0") (class "Default")
      (node (ref "U14") (pin "9") (pinfunction "SDO/AD0_9") (pintype "input"))
      (node (ref "U7") (pin "28") (pinfunction "IO17_28") (pintype "input"))
    )
    (net (code "23") (name "IMU_INT") (class "Default")
      (node (ref "R41") (pin "2") (pinfunction "2_2") (pintype "input"))
      (node (ref "U18") (pin "3") (pinfunction "D_3") (pintype "input"))
      (node (ref "U7") (pin "26") (pinfunction "IO4_26") (pintype "input"))
    )
    (net (code "24") (name "INT1.8") (class "Default")
      (node (ref "R42") (pin "2") (pinfunction "2_2") (pintype "input"))
      (node (ref "U14") (pin "12") (pinfunction "INT1_12") (pintype "input"))
      (node (ref "U18") (pin "2") (pinfunction "S_2") (pintype "input"))
    )
    (net (code "25") (name "LED") (class "Default")
      (node (ref "R44") (pin "1") (pinfunction "1_1") (pintype "input"))
      (node (ref "U7") (pin "16") (pinfunction "IO13_16") (pintype "input"))
    )
    (net (code "26") (name "Net-(LDO1-CE)") (class "Default")
      (node (ref "C18") (pin "2") (pinfunction "2_2") (pintype "input"))
      (node (ref "D4") (pin "1") (pinfunction "1_1") (pintype "input"))
      (node (ref "LDO1") (pin "1") (pinfunction "VIN_1") (pintype "input"))
      (node (ref "LDO1") (pin "3") (pinfunction "CE_3") (pintype "input"))
      (node (ref "Q1") (pin "2") (pinfunction "S_2") (pintype "input"))
    )
    (net (code "27") (name "Net-(LED1-A)") (class "Default")
      (node (ref "LED1") (pin "2") (pinfunction "A_2") (pintype "input"))
      (node (ref "R26") (pin "1") (pinfunction "1_1") (pintype "input"))
    )
    (net (code "28") (name "Net-(LED1-K)") (class "Default")
      (node (ref "LED1") (pin "1") (pinfunction "K_1") (pintype "input"))
      (node (ref "U12") (pin "1") (pinfunction "CHRG_1") (pintype "input"))
    )
    (net (code "29") (name "Net-(LED3-A)") (class "Default")
      (node (ref "LED3") (pin "2") (pinfunction "A_2") (pintype "input"))
      (node (ref "R35") (pin "2") (pinfunction "2_2") (pintype "input"))
    )
    (net (code "30") (name "Net-(LED4-A)") (class "Default")
      (node (ref "LED4") (pin "2") (pinfunction "A_2") (pintype "input"))
      (node (ref "R36") (pin "2") (pinfunction "2_2") (pintype "input"))
    )
    (net (code "31") (name "Net-(LED5-A)") (class "Default")
      (node (ref "LED5") (pin "2") (pinfunction "A_2") (pintype "input"))
      (node (ref "R44") (pin "2") (pinfunction "2_2") (pintype "input"))
    )
    (net (code "32") (name "Net-(Q2-B)") (class "Default")
      (node (ref "Q2") (pin "1") (pinfunction "B_1") (pintype "input"))
      (node (ref "R3") (pin "1") (pinfunction "1_1") (pintype "input"))
    )
    (net (code "33") (name "Net-(Q3-B)") (class "Default")
      (node (ref "Q3") (pin "1") (pinfunction "B_1") (pintype "input"))
      (node (ref "R2") (pin "1") (pinfunction "1_1") (pintype "input"))
    )
    (net (code "34") (name "Net-(U2-RSTb)") (class "Default")
      (node (ref "R6") (pin "1") (pinfunction "1_1") (pintype "input"))
      (node (ref "U2") (pin "9") (pinfunction "RSTb_9") (pintype "input"))
    )
    (net (code "35") (name "Net-(U2-SUSPENDb)") (class "Default")
      (node (ref "R7") (pin "1") (pinfunction "1_1") (pintype "input"))
      (node (ref "U2") (pin "11") (pinfunction "SUSPENDb_11") (pintype "input"))
    )
    (net (code "36") (name "Net-(U2-VBUS)") (class "Default")
      (node (ref "R4") (pin "2") (pinfunction "2_2") (pintype "input"))
      (node (ref "R5") (pin "1") (pinfunction "1_1") (pintype "input"))
      (node (ref "U2") (pin "8") (pinfunction "VBUS_8") (pintype "input"))
    )
    (net (code "37") (name "Net-(U7-IO21)") (class "Default")
      (node (ref "R46") (pin "2") (pinfunction "2_2") (pintype "input"))
      (node (ref "U7") (pin "33") (pinfunction "IO21_33") (pintype "input"))
    )
    (net (code "38") (name "Net-(U7-IO22)") (class "Default")
      (node (ref "R45") (pin "2") (pinfunction "2_2") (pintype "input"))
      (node (ref "U7") (pin "36") (pinfunction "IO22_36") (pintype "input"))
    )
    (net (code "39") (name "Net-(U12-PROG)") (class "Default")
      (node (ref "R27") (pin "2") (pinfunction "2_2") (pintype "input"))
      (node (ref "U12") (pin "5") (pinfunction "PROG_5") (pintype "input"))
    )
    (net (code "40") (name "Net-(U14-REGOUT)") (class "Default")
      (node (ref "C25") (pin "2") (pinfunction "2_2") (pintype "input"))
      (node (ref "U14") (pin "10") (pinfunction "REGOUT_10") (pintype "input"))
    )
    (net (code "41") (name "Net-(U14-nCS)") (class "Default")
      (node (ref "R43") (pin "1") (pinfunction "1_1") (pintype "input"))
      (node (ref "U14") (pin "22") (pinfunction "nCS_22") (pintype "input"))
    )
    (net (code "42") (name "RGB_LED") (class "Default")
      (node (ref "LED2") (pin "4") (pinfunction "DIN_4") (pintype "input"))
      (node (ref "R30") (pin "2") (pinfunction "2_2") (pintype "input"))
      (node (ref "U7") (pin "27") (pinfunction "IO16_27") (pintype "input"))
    )
    (net (code "43") (name "RTS") (class "Default")
      (node (ref "Q3") (pin "2") (pinfunction "E_2") (pintype "input"))
      (node (ref "R3") (pin "2") (pinfunction "2_2") (pintype "input"))
      (node (ref "U2") (pin "24") (pinfunction "RTS_24") (pintype "input"))
    )
    (net (code "44") (name "RXD0") (class "Default")
      (node (ref "U2") (pin "25") (pinfunction "RXD_25") (pintype "input"))
      (node (ref "U7") (pin "35") (pinfunction "TXD0_35") (pintype "input"))
    )
    (net (code "45") (name "S0") (class "Default")
      (node (ref "U19") (pin "10") (pinfunction "S0_10") (pintype "unspecified"))
      (node (ref "U7") (pin "30") (pinfunction "IO18_30") (pintype "input"))
    )
    (net (code "46") (name "S1") (class "Default")
      (node (ref "U19") (pin "11") (pinfunction "S1_11") (pintype "unspecified"))
      (node (ref "U7") (pin "29") (pinfunction "IO5_29") (pintype "input"))
    )
    (net (code "47") (name "S2") (class "Default")
      (node (ref "U19") (pin "14") (pinfunction "S2_14") (pintype "unspecified"))
      (node (ref "U7") (pin "31") (pinfunction "IO19_31") (pintype "input"))
    )
    (net (code "48") (name "S3") (class "Default")
      (node (ref "U19") (pin "13") (pinfunction "S3_13") (pintype "unspecified"))
      (node (ref "U7") (pin "24") (pinfunction "IO2_24") (pintype "input"))
    )
    (net (code "49") (name "SCL") (class "Default")
      (node (ref "R39") (pin "2") (pinfunction "2_2") (pintype "input"))
      (node (ref "R45") (pin "1") (pinfunction "1_1") (pintype "input"))
      (node (ref "U17") (pin "3") (pinfunction "D_3") (pintype "input"))
    )
    (net (code "50") (name "SCL1.8") (class "Default")
      (node (ref "R40") (pin "2") (pinfunction "2_2") (pintype "input"))
      (node (ref "U14") (pin "23") (pinfunction "SCL/SCLK_23") (pintype "input"))
      (node (ref "U17") (pin "2") (pinfunction "S_2") (pintype "input"))
    )
    (net (code "51") (name "SDA") (class "Default")
      (node (ref "R37") (pin "2") (pinfunction "2_2") (pintype "input"))
      (node (ref "R46") (pin "1") (pinfunction "1_1") (pintype "input"))
      (node (ref "U16") (pin "3") (pinfunction "D_3") (pintype "input"))
    )
    (net (code "52") (name "SDA1.8") (class "Default")
      (node (ref "R38") (pin "2") (pinfunction "2_2") (pintype "input"))
      (node (ref "U14") (pin "24") (pinfunction "SDA/SDI_24") (pintype "input"))
      (node (ref "U16") (pin "2") (pinfunction "S_2") (pintype "input"))
    )
    (net (code "53") (name "SIG") (class "Default")
      (node (ref "U19") (pin "1") (pinfunction "COMMON_INOUT/OUTPUT_1") (pintype "unspecified"))
      (node (ref "U7") (pin "8") (pinfunction "IO32_8") (pintype "input"))
    )
    (net (code "54") (name "TXD0") (class "Default")
      (node (ref "U2") (pin "26") (pinfunction "TXD_26") (pintype "input"))
      (node (ref "U7") (pin "34") (pinfunction "RXD0_34") (pintype "input"))
    )
    (net (code "55") (name "USB_D+") (class "Default")
      (node (ref "D2") (pin "2") (pinfunction "2_2") (pintype "input"))
      (node (ref "R22") (pin "1") (pinfunction "1_1") (pintype "input"))
      (node (ref "USB2") (pin "A6") (pinfunction "DP1_A6") (pintype "input"))
      (node (ref "USB2") (pin "B6") (pinfunction "DP2_B6") (pintype "input"))
    )
    (net (code "56") (name "USB_D-") (class "Default")
      (node (ref "D3") (pin "2") (pinfunction "2_2") (pintype "input"))
      (node (ref "R21") (pin "1") (pinfunction "1_1") (pintype "input"))
      (node (ref "USB2") (pin "A7") (pinfunction "DN1_A7") (pintype "input"))
      (node (ref "USB2") (pin "B7") (pinfunction "DN2_B7") (pintype "input"))
    )
    (net (code "57") (name "USB_DN") (class "Default")
      (node (ref "R21") (pin "2") (pinfunction "2_2") (pintype "input"))
      (node (ref "U2") (pin "5") (pinfunction "D-_5") (pintype "input"))
    )
    (net (code "58") (name "USB_DP") (class "Default")
      (node (ref "R22") (pin "2") (pinfunction "2_2") (pintype "input"))
      (node (ref "U2") (pin "4") (pinfunction "D+_4") (pintype "input"))
    )
    (net (code "59") (name "VBAT") (class "Default")
      (node (ref "H1") (pin "1") (pinfunction "1_1") (pintype "input"))
      (node (ref "Q1") (pin "3") (pinfunction "D_3") (pintype "input"))
      (node (ref "R29") (pin "1") (pinfunction "1_1") (pintype "input"))
      (node (ref "U12") (pin "3") (pinfunction "BAT_3") (pintype "input"))
    )
    (net (code "60") (name "VBUS") (class "Default")
      (node (ref "D1") (pin "2") (pinfunction "2_2") (pintype "input"))
      (node (ref "D4") (pin "2") (pinfunction "2_2") (pintype "input"))
      (node (ref "Q1") (pin "1") (pinfunction "G_1") (pintype "input"))
      (node (ref "R25") (pin "2") (pinfunction "2_2") (pintype "input"))
      (node (ref "R26") (pin "2") (pinfunction "2_2") (pintype "input"))
      (node (ref "R4") (pin "1") (pinfunction "1_1") (pintype "input"))
      (node (ref "U12") (pin "4") (pinfunction "VCC_4") (pintype "input"))
      (node (ref "USB2") (pin "A4") (pinfunction "VBUS_A4") (pintype "input"))
      (node (ref "USB2") (pin "A9") (pinfunction "VBUS_A9") (pintype "input"))
      (node (ref "USB2") (pin "B4") (pinfunction "VBUS_B4") (pintype "input"))
      (node (ref "USB2") (pin "B9") (pinfunction "VBUS_B9") (pintype "input"))
    )
    (net (code "61") (name "VDD1.8") (class "Default")
      (node (ref "C23") (pin "2") (pinfunction "2_2") (pintype "input"))
      (node (ref "R36") (pin "1") (pinfunction "1_1") (pintype "input"))
      (node (ref "R38") (pin "1") (pinfunction "1_1") (pintype "input"))
      (node (ref "R40") (pin "1") (pinfunction "1_1") (pintype "input"))
      (node (ref "R42") (pin "1") (pinfunction "1_1") (pintype "input"))
      (node (ref "R43") (pin "2") (pinfunction "2_2") (pintype "input"))
      (node (ref "U13") (pin "5") (pinfunction "VOUT_5") (pintype "input"))
      (node (ref "U14") (pin "13") (pinfunction "VDD_13") (pintype "input"))
      (node (ref "U14") (pin "8") (pinfunction "VDDIO_8") (pintype "input"))
      (node (ref "U16") (pin "1") (pinfunction "G_1") (pintype "input"))
      (node (ref "U17") (pin "1") (pinfunction "G_1") (pintype "input"))
      (node (ref "U18") (pin "1") (pinfunction "G_1") (pintype "input"))
    )
    (net (code "62") (name "VDD33") (class "Default")
      (node (ref "C24") (pin "2") (pinfunction "2_2") (pintype "input"))
      (node (ref "C26") (pin "2") (pinfunction "2_2") (pintype "input"))
      (node (ref "C27") (pin "2") (pinfunction "2_2") (pintype "input"))
      (node (ref "C4") (pin "2") (pinfunction "2_2") (pintype "input"))
      (node (ref "C5") (pin "2") (pinfunction "2_2") (pintype "input"))
      (node (ref "FPC1") (pin "14") (pinfunction "14_14") (pintype "input"))
      (node (ref "FPC1") (pin "6") (pinfunction "6_6") (pintype "input"))
      (node (ref "FPC2") (pin "15") (pinfunction "15_15") (pintype "input"))
      (node (ref "FPC2") (pin "7") (pinfunction "7_7") (pintype "input"))
      (node (ref "LED2") (pin "1") (pinfunction "VDD_1") (pintype "input"))
      (node (ref "R1") (pin "2") (pinfunction "2_2") (pintype "input"))
      (node (ref "R30") (pin "1") (pinfunction "1_1") (pintype "input"))
      (node (ref "R35") (pin "1") (pinfunction "1_1") (pintype "input"))
      (node (ref "R37") (pin "1") (pinfunction "1_1") (pintype "input"))
      (node (ref "R39") (pin "1") (pinfunction "1_1") (pintype "input"))
      (node (ref "R41") (pin "1") (pinfunction "1_1") (pintype "input"))
      (node (ref "R6") (pin "2") (pinfunction "2_2") (pintype "input"))
      (node (ref "SW5") (pin "3") (pinfunction "3_3") (pintype "input"))
      (node (ref "U13") (pin "1") (pinfunction "VIN_1") (pintype "input"))
      (node (ref "U13") (pin "3") (pinfunction "CE_3") (pintype "input"))
      (node (ref "U19") (pin "24") (pinfunction "VCC_24") (pintype "unspecified"))
      (node (ref "U2") (pin "6") (pinfunction "VDD_6") (pintype "input"))
      (node (ref "U2") (pin "7") (pinfunction "VREGIN_7") (pintype "input"))
      (node (ref "U7") (pin "2") (pinfunction "3V3_2") (pintype "input"))
    )
    (net (code "63") (name "VDDOUT") (class "Default")
      (node (ref "C19") (pin "2") (pinfunction "2_2") (pintype "input"))
      (node (ref "C20") (pin "2") (pinfunction "2_2") (pintype "input"))
      (node (ref "LDO1") (pin "5") (pinfunction "VOUT_5") (pintype "input"))
      (node (ref "SW5") (pin "2") (pinfunction "2_2") (pintype "input"))
    )
    (net (code "64") (name "unconnected-(FPC1-Pad21)") (class "Default")
      (node (ref "FPC1") (pin "21") (pinfunction "21_21") (pintype "input"))
    )
    (net (code "65") (name "unconnected-(FPC1-Pad22)") (class "Default")
      (node (ref "FPC1") (pin "22") (pinfunction "22_22") (pintype "input"))
    )
    (net (code "66") (name "unconnected-(FPC2-Pad21)") (class "Default")
      (node (ref "FPC2") (pin "21") (pinfunction "21_21") (pintype "input"))
    )
    (net (code "67") (name "unconnected-(FPC2-Pad22)") (class "Default")
      (node (ref "FPC2") (pin "22") (pinfunction "22_22") (pintype "input"))
    )
    (net (code "68") (name "unconnected-(LDO1-NC-Pad4)") (class "Default")
      (node (ref "LDO1") (pin "4") (pinfunction "NC_4") (pintype "input"))
    )
    (net (code "69") (name "unconnected-(LED2-DOUT-Pad2)") (class "Default")
      (node (ref "LED2") (pin "2") (pinfunction "DOUT_2") (pintype "input"))
    )
    (net (code "70") (name "unconnected-(SW5-Pad1)") (class "Default")
      (node (ref "SW5") (pin "1") (pinfunction "1_1") (pintype "input"))
    )
    (net (code "71") (name "unconnected-(U2-CHR0-Pad15)") (class "Default")
      (node (ref "U2") (pin "15") (pinfunction "CHR0_15") (pintype "input"))
    )
    (net (code "72") (name "unconnected-(U2-CHR1-Pad14)") (class "Default")
      (node (ref "U2") (pin "14") (pinfunction "CHR1_14") (pintype "input"))
    )
    (net (code "73") (name "unconnected-(U2-CHREN-Pad13)") (class "Default")
      (node (ref "U2") (pin "13") (pinfunction "CHREN_13") (pintype "input"))
    )
    (net (code "74") (name "unconnected-(U2-CTS-Pad23)") (class "Default")
      (node (ref "U2") (pin "23") (pinfunction "CTS_23") (pintype "input"))
    )
    (net (code "75") (name "unconnected-(U2-DCD-Pad1)") (class "Default")
      (node (ref "U2") (pin "1") (pinfunction "DCD_1") (pintype "input"))
    )
    (net (code "76") (name "unconnected-(U2-DSR-Pad27)") (class "Default")
      (node (ref "U2") (pin "27") (pinfunction "DSR_27") (pintype "input"))
    )
    (net (code "77") (name "unconnected-(U2-GPIO.0{slash}TXT-Pad19)") (class "Default")
      (node (ref "U2") (pin "19") (pinfunction "GPIO.0/TXT_19") (pintype "input"))
    )
    (net (code "78") (name "unconnected-(U2-GPIO.1{slash}RXT-Pad18)") (class "Default")
      (node (ref "U2") (pin "18") (pinfunction "GPIO.1/RXT_18") (pintype "input"))
    )
    (net (code "79") (name "unconnected-(U2-GPIO.2{slash}RS485-Pad17)") (class "Default")
      (node (ref "U2") (pin "17") (pinfunction "GPIO.2/RS485_17") (pintype "input"))
    )
    (net (code "80") (name "unconnected-(U2-GPIO.3{slash}WAKEUP-Pad16)") (class "Default")
      (node (ref "U2") (pin "16") (pinfunction "GPIO.3/WAKEUP_16") (pintype "input"))
    )
    (net (code "81") (name "unconnected-(U2-GPIO.4-Pad22)") (class "Default")
      (node (ref "U2") (pin "22") (pinfunction "GPIO.4_22") (pintype "input"))
    )
    (net (code "82") (name "unconnected-(U2-GPIO.5-Pad21)") (class "Default")
      (node (ref "U2") (pin "21") (pinfunction "GPIO.5_21") (pintype "input"))
    )
    (net (code "83") (name "unconnected-(U2-GPIO.6-Pad20)") (class "Default")
      (node (ref "U2") (pin "20") (pinfunction "GPIO.6_20") (pintype "input"))
    )
    (net (code "84") (name "unconnected-(U2-NC-Pad10)") (class "Default")
      (node (ref "U2") (pin "10") (pinfunction "NC_10") (pintype "input"))
    )
    (net (code "85") (name "unconnected-(U2-RI{slash}CLK-Pad2)") (class "Default")
      (node (ref "U2") (pin "2") (pinfunction "RI/CLK_2") (pintype "input"))
    )
    (net (code "86") (name "unconnected-(U2-SUSPEND-Pad12)") (class "Default")
      (node (ref "U2") (pin "12") (pinfunction "SUSPEND_12") (pintype "input"))
    )
    (net (code "87") (name "unconnected-(U7-IO12-Pad14)") (class "Default")
      (node (ref "U7") (pin "14") (pinfunction "IO12_14") (pintype "input"))
    )
    (net (code "88") (name "unconnected-(U7-IO14-Pad13)") (class "Default")
      (node (ref "U7") (pin "13") (pinfunction "IO14_13") (pintype "input"))
    )
    (net (code "89") (name "unconnected-(U7-IO15-Pad23)") (class "Default")
      (node (ref "U7") (pin "23") (pinfunction "IO15_23") (pintype "input"))
    )
    (net (code "90") (name "unconnected-(U7-IO23-Pad37)") (class "Default")
      (node (ref "U7") (pin "37") (pinfunction "IO23_37") (pintype "input"))
    )
    (net (code "91") (name "unconnected-(U7-IO25-Pad10)") (class "Default")
      (node (ref "U7") (pin "10") (pinfunction "IO25_10") (pintype "input"))
    )
    (net (code "92") (name "unconnected-(U7-IO26-Pad11)") (class "Default")
      (node (ref "U7") (pin "11") (pinfunction "IO26_11") (pintype "input"))
    )
    (net (code "93") (name "unconnected-(U7-IO27-Pad12)") (class "Default")
      (node (ref "U7") (pin "12") (pinfunction "IO27_12") (pintype "input"))
    )
    (net (code "94") (name "unconnected-(U7-IO33-Pad9)") (class "Default")
      (node (ref "U7") (pin "9") (pinfunction "IO33_9") (pintype "input"))
    )
    (net (code "95") (name "unconnected-(U7-IO35-Pad7)") (class "Default")
      (node (ref "U7") (pin "7") (pinfunction "IO35_7") (pintype "input"))
    )
    (net (code "96") (name "unconnected-(U7-NC-Pad17)") (class "Default")
      (node (ref "U7") (pin "17") (pinfunction "NC_17") (pintype "input"))
    )
    (net (code "97") (name "unconnected-(U7-NC-Pad18)") (class "Default")
      (node (ref "U7") (pin "18") (pinfunction "NC_18") (pintype "input"))
    )
    (net (code "98") (name "unconnected-(U7-NC-Pad19)") (class "Default")
      (node (ref "U7") (pin "19") (pinfunction "NC_19") (pintype "input"))
    )
    (net (code "99") (name "unconnected-(U7-NC-Pad20)") (class "Default")
      (node (ref "U7") (pin "20") (pinfunction "NC_20") (pintype "input"))
    )
    (net (code "100") (name "unconnected-(U7-NC-Pad21)") (class "Default")
      (node (ref "U7") (pin "21") (pinfunction "NC_21") (pintype "input"))
    )
    (net (code "101") (name "unconnected-(U7-NC-Pad22)") (class "Default")
      (node (ref "U7") (pin "22") (pinfunction "NC_22") (pintype "input"))
    )
    (net (code "102") (name "unconnected-(U7-NC-Pad32)") (class "Default")
      (node (ref "U7") (pin "32") (pinfunction "NC_32") (pintype "input"))
    )
    (net (code "103") (name "unconnected-(U7-SENSOR_VN-Pad5)") (class "Default")
      (node (ref "U7") (pin "5") (pinfunction "SENSOR_VN_5") (pintype "input"))
    )
    (net (code "104") (name "unconnected-(U7-SENSOR_VP-Pad4)") (class "Default")
      (node (ref "U7") (pin "4") (pinfunction "SENSOR_VP_4") (pintype "input"))
    )
    (net (code "105") (name "unconnected-(U13-NC-Pad4)") (class "Default")
      (node (ref "U13") (pin "4") (pinfunction "NC_4") (pintype "input"))
    )
    (net (code "106") (name "unconnected-(U14-AUX_CL-Pad7)") (class "Default")
      (node (ref "U14") (pin "7") (pinfunction "AUX_CL_7") (pintype "input"))
    )
    (net (code "107") (name "unconnected-(U14-AUX_DA-Pad21)") (class "Default")
      (node (ref "U14") (pin "21") (pinfunction "AUX_DA_21") (pintype "input"))
    )
    (net (code "108") (name "unconnected-(U14-FSYNC-Pad11)") (class "Default")
      (node (ref "U14") (pin "11") (pinfunction "FSYNC_11") (pintype "input"))
    )
    (net (code "109") (name "unconnected-(U14-NC-Pad1)") (class "Default")
      (node (ref "U14") (pin "1") (pinfunction "NC_1") (pintype "input"))
    )
    (net (code "110") (name "unconnected-(U14-NC-Pad2)") (class "Default")
      (node (ref "U14") (pin "2") (pinfunction "NC_2") (pintype "input"))
    )
    (net (code "111") (name "unconnected-(U14-NC-Pad3)") (class "Default")
      (node (ref "U14") (pin "3") (pinfunction "NC_3") (pintype "input"))
    )
    (net (code "112") (name "unconnected-(U14-NC-Pad4)") (class "Default")
      (node (ref "U14") (pin "4") (pinfunction "NC_4") (pintype "input"))
    )
    (net (code "113") (name "unconnected-(U14-NC-Pad5)") (class "Default")
      (node (ref "U14") (pin "5") (pinfunction "NC_5") (pintype "input"))
    )
    (net (code "114") (name "unconnected-(U14-NC-Pad6)") (class "Default")
      (node (ref "U14") (pin "6") (pinfunction "NC_6") (pintype "input"))
    )
    (net (code "115") (name "unconnected-(U14-NC-Pad14)") (class "Default")
      (node (ref "U14") (pin "14") (pinfunction "NC_14") (pintype "input"))
    )
    (net (code "116") (name "unconnected-(U14-NC-Pad15)") (class "Default")
      (node (ref "U14") (pin "15") (pinfunction "NC_15") (pintype "input"))
    )
    (net (code "117") (name "unconnected-(U14-NC-Pad16)") (class "Default")
      (node (ref "U14") (pin "16") (pinfunction "NC_16") (pintype "input"))
    )
    (net (code "118") (name "unconnected-(U14-NC-Pad17)") (class "Default")
      (node (ref "U14") (pin "17") (pinfunction "NC_17") (pintype "input"))
    )
    (net (code "119") (name "unconnected-(U14-RESV-Pad19)") (class "Default")
      (node (ref "U14") (pin "19") (pinfunction "RESV_19") (pintype "input"))
    )
    (net (code "120") (name "unconnected-(USB2-CC1-PadA5)") (class "Default")
      (node (ref "USB2") (pin "A5") (pinfunction "CC1_A5") (pintype "input"))
    )
    (net (code "121") (name "unconnected-(USB2-CC2-PadB5)") (class "Default")
      (node (ref "USB2") (pin "B5") (pinfunction "CC2_B5") (pintype "input"))
    )
    (net (code "122") (name "unconnected-(USB2-SUB1-PadA8)") (class "Default")
      (node (ref "USB2") (pin "A8") (pinfunction "SUB1_A8") (pintype "input"))
    )
    (net (code "123") (name "unconnected-(USB2-SUB2-PadB8)") (class "Default")
      (node (ref "USB2") (pin "B8") (pinfunction "SUB2_B8") (pintype "input"))
    )
  )
)
